# LcdModule-16x2_1V0.net
KiCad netlist of a schematic drawn in EAGLE
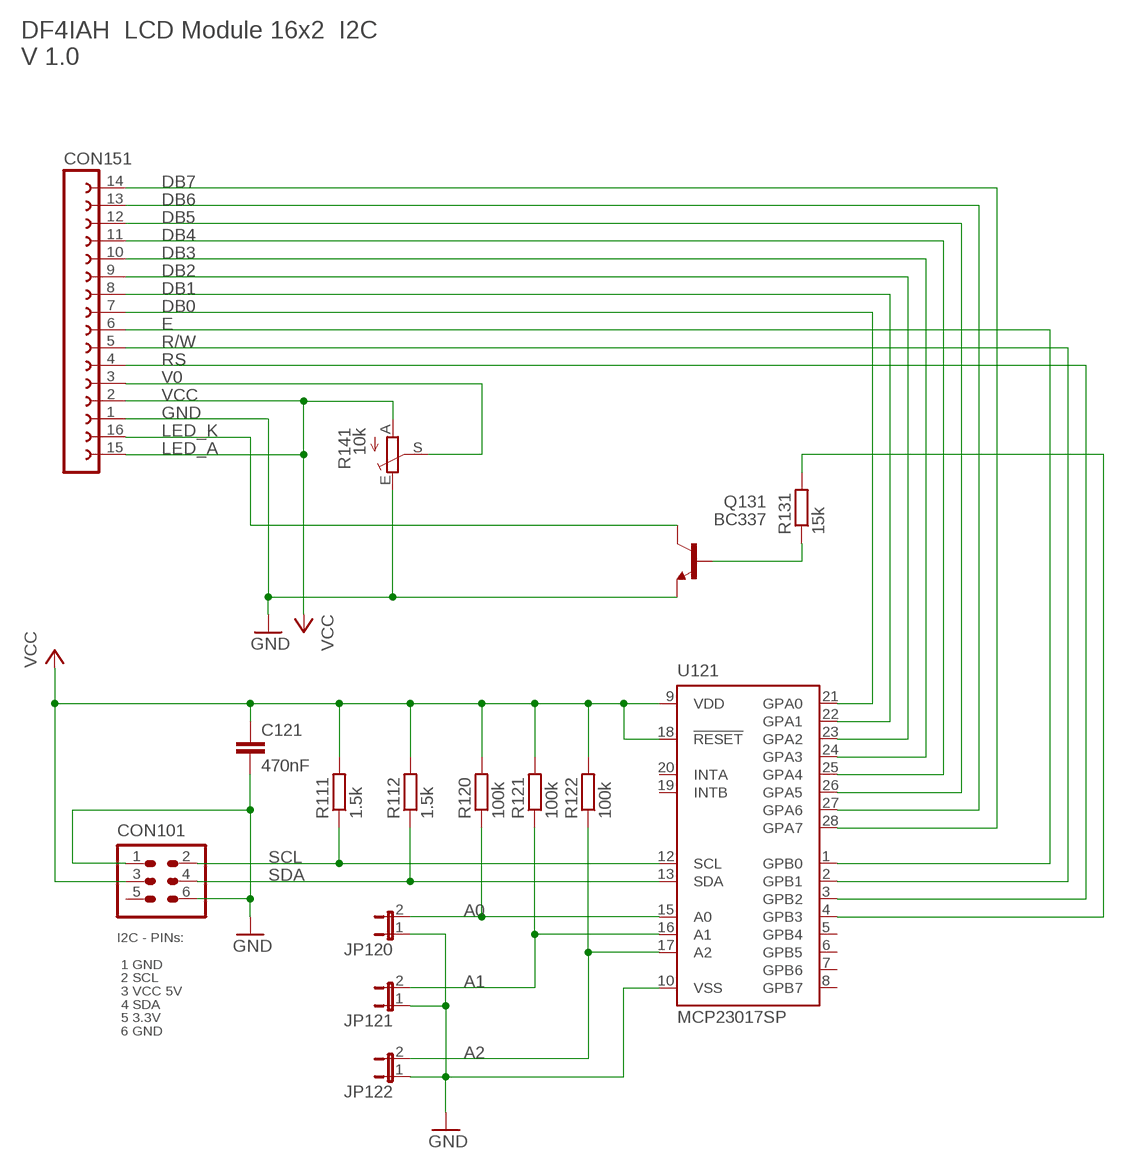
[diagram p0: schematic, sheet 1]
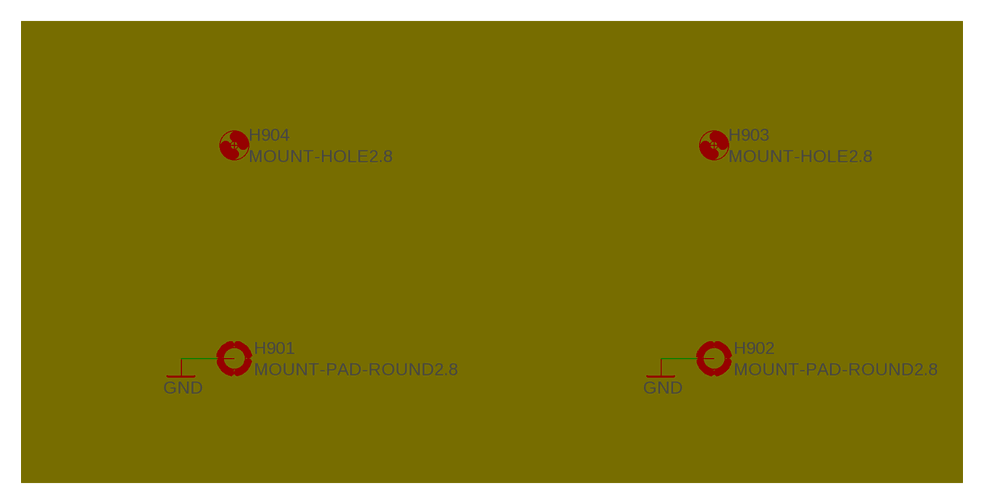
[diagram p1: schematic, sheet 2]

(export (version "E")
  (design (tool "Eeschema 10.0.6"))
  (components
    (comp (ref "C121")
      (value "470nF")
      (footprint "eagle-import:C0805")
      (libsource (lib "eagle-import") (part "C-EUC0805"))
    )
    (comp (ref "CON101")
      (value "HEADER-2X3SMD")
      (footprint "eagle-import:2X03SMD")
      (libsource (lib "eagle-import") (part "HEADER-2X3SMD"))
    )
    (comp (ref "CON151")
      (value "CON_LCDBRD_16W")
      (footprint "eagle-import:CON_LCDBRD_16W")
      (libsource (lib "eagle-import") (part "CON_LCDBRD_16W"))
    )
    (comp (ref "JP120")
      (value "JP1E")
      (footprint "eagle-import:JP1")
      (libsource (lib "eagle-import") (part "JP1E"))
    )
    (comp (ref "JP121")
      (value "JP1E")
      (footprint "eagle-import:JP1")
      (libsource (lib "eagle-import") (part "JP1E"))
    )
    (comp (ref "JP122")
      (value "JP1E")
      (footprint "eagle-import:JP1")
      (libsource (lib "eagle-import") (part "JP1E"))
    )
    (comp (ref "Q131")
      (value "BC337")
      (footprint "eagle-import:TO92")
      (libsource (lib "eagle-import") (part "BC337"))
    )
    (comp (ref "R111")
      (value "1.5k")
      (footprint "eagle-import:R0805")
      (libsource (lib "eagle-import") (part "R-EU_R0805"))
    )
    (comp (ref "R112")
      (value "1.5k")
      (footprint "eagle-import:R0805")
      (libsource (lib "eagle-import") (part "R-EU_R0805"))
    )
    (comp (ref "R120")
      (value "100k")
      (footprint "eagle-import:R0805")
      (libsource (lib "eagle-import") (part "R-EU_R0805"))
    )
    (comp (ref "R121")
      (value "100k")
      (footprint "eagle-import:R0805")
      (libsource (lib "eagle-import") (part "R-EU_R0805"))
    )
    (comp (ref "R122")
      (value "100k")
      (footprint "eagle-import:R0805")
      (libsource (lib "eagle-import") (part "R-EU_R0805"))
    )
    (comp (ref "R131")
      (value "15k")
      (footprint "eagle-import:R0805")
      (libsource (lib "eagle-import") (part "R-EU_R0805"))
    )
    (comp (ref "R141")
      (value "10k")
      (footprint "eagle-import:PT-10")
      (libsource (lib "eagle-import") (part "TRIM_EU-PT10"))
    )
    (comp (ref "U121")
      (value "MCP23017SP")
      (footprint "eagle-import:DIL28-3")
      (fields (field (name "MF") "MICROCHIP") (field (name "MPN") "MCP23017-E/SP"))
      (libsource (lib "eagle-import") (part "MCP23017SP"))
    )
    (comp (ref "H901")
      (value "MOUNT-PAD-ROUND2.8")
      (footprint "eagle-import:2,8-PAD")
      (libsource (lib "eagle-import") (part "MOUNT-PAD-ROUND2.8"))
    )
    (comp (ref "H902")
      (value "MOUNT-PAD-ROUND2.8")
      (footprint "eagle-import:2,8-PAD")
      (libsource (lib "eagle-import") (part "MOUNT-PAD-ROUND2.8"))
    )
    (comp (ref "H903")
      (value "MOUNT-HOLE2.8")
      (footprint "eagle-import:2,8")
      (libsource (lib "eagle-import") (part "MOUNT-HOLE2.8"))
    )
    (comp (ref "H904")
      (value "MOUNT-HOLE2.8")
      (footprint "eagle-import:2,8")
      (libsource (lib "eagle-import") (part "MOUNT-HOLE2.8"))
    )
  )
  (nets
    (net (code "1") (name "A0") (class "Default")
      (node (ref "JP120") (pin "2") (pinfunction "2_2") (pintype "passive"))
      (node (ref "R120") (pin "1") (pinfunction "1_1") (pintype "passive"))
      (node (ref "U121") (pin "15") (pinfunction "A0_15") (pintype "input"))
    )
    (net (code "2") (name "A1") (class "Default")
      (node (ref "JP121") (pin "2") (pinfunction "2_2") (pintype "passive"))
      (node (ref "R121") (pin "1") (pinfunction "1_1") (pintype "passive"))
      (node (ref "U121") (pin "16") (pinfunction "A1_16") (pintype "input"))
    )
    (net (code "3") (name "A2") (class "Default")
      (node (ref "JP122") (pin "2") (pinfunction "2_2") (pintype "passive"))
      (node (ref "R122") (pin "1") (pinfunction "1_1") (pintype "passive"))
      (node (ref "U121") (pin "17") (pinfunction "A2_17") (pintype "input"))
    )
    (net (code "4") (name "DB0") (class "Default")
      (node (ref "CON151") (pin "7") (pinfunction "7_7") (pintype "passive"))
      (node (ref "U121") (pin "21") (pinfunction "GPA0_21") (pintype "bidirectional"))
    )
    (net (code "5") (name "DB1") (class "Default")
      (node (ref "CON151") (pin "8") (pinfunction "8_8") (pintype "passive"))
      (node (ref "U121") (pin "22") (pinfunction "GPA1_22") (pintype "bidirectional"))
    )
    (net (code "6") (name "DB2") (class "Default")
      (node (ref "CON151") (pin "9") (pinfunction "9_9") (pintype "passive"))
      (node (ref "U121") (pin "23") (pinfunction "GPA2_23") (pintype "bidirectional"))
    )
    (net (code "7") (name "DB3") (class "Default")
      (node (ref "CON151") (pin "10") (pinfunction "10_10") (pintype "passive"))
      (node (ref "U121") (pin "24") (pinfunction "GPA3_24") (pintype "bidirectional"))
    )
    (net (code "8") (name "DB4") (class "Default")
      (node (ref "CON151") (pin "11") (pinfunction "11_11") (pintype "passive"))
      (node (ref "U121") (pin "25") (pinfunction "GPA4_25") (pintype "bidirectional"))
    )
    (net (code "9") (name "DB5") (class "Default")
      (node (ref "CON151") (pin "12") (pinfunction "12_12") (pintype "passive"))
      (node (ref "U121") (pin "26") (pinfunction "GPA5_26") (pintype "bidirectional"))
    )
    (net (code "10") (name "DB6") (class "Default")
      (node (ref "CON151") (pin "13") (pinfunction "13_13") (pintype "passive"))
      (node (ref "U121") (pin "27") (pinfunction "GPA6_27") (pintype "bidirectional"))
    )
    (net (code "11") (name "DB7") (class "Default")
      (node (ref "CON151") (pin "14") (pinfunction "14_14") (pintype "passive"))
      (node (ref "U121") (pin "28") (pinfunction "GPA7_28") (pintype "bidirectional"))
    )
    (net (code "12") (name "E") (class "Default")
      (node (ref "CON151") (pin "6") (pinfunction "6_6") (pintype "passive"))
      (node (ref "U121") (pin "1") (pinfunction "GPB0_1") (pintype "bidirectional"))
    )
    (net (code "13") (name "GND") (class "Default")
      (node (ref "C121") (pin "2") (pinfunction "2_2") (pintype "passive"))
      (node (ref "CON101") (pin "1") (pinfunction "1_1") (pintype "passive"))
      (node (ref "CON101") (pin "6") (pinfunction "6_6") (pintype "passive"))
      (node (ref "CON151") (pin "1") (pinfunction "1_1") (pintype "passive"))
      (node (ref "H901") (pin "B2,8") (pinfunction "MOUNT_B2,8") (pintype "passive"))
      (node (ref "H902") (pin "B2,8") (pinfunction "MOUNT_B2,8") (pintype "passive"))
      (node (ref "JP120") (pin "1") (pinfunction "1_1") (pintype "passive"))
      (node (ref "JP121") (pin "1") (pinfunction "1_1") (pintype "passive"))
      (node (ref "JP122") (pin "1") (pinfunction "1_1") (pintype "passive"))
      (node (ref "Q131") (pin "1") (pinfunction "E_1") (pintype "passive"))
      (node (ref "R141") (pin "E") (pinfunction "E_E") (pintype "passive"))
      (node (ref "U121") (pin "10") (pinfunction "VSS_10") (pintype "power_in"))
    )
    (net (code "14") (name "LED_K") (class "Default")
      (node (ref "CON151") (pin "16") (pinfunction "16_16") (pintype "passive"))
      (node (ref "Q131") (pin "3") (pinfunction "C_3") (pintype "passive"))
    )
    (net (code "15") (name "Net-(Q131-B)") (class "Default")
      (node (ref "Q131") (pin "2") (pinfunction "B_2") (pintype "passive"))
      (node (ref "R131") (pin "1") (pinfunction "1_1") (pintype "passive"))
    )
    (net (code "16") (name "Net-(U121-GPB3)") (class "Default")
      (node (ref "R131") (pin "2") (pinfunction "2_2") (pintype "passive"))
      (node (ref "U121") (pin "4") (pinfunction "GPB3_4") (pintype "bidirectional"))
    )
    (net (code "17") (name "RS") (class "Default")
      (node (ref "CON151") (pin "4") (pinfunction "4_4") (pintype "passive"))
      (node (ref "U121") (pin "3") (pinfunction "GPB2_3") (pintype "bidirectional"))
    )
    (net (code "18") (name "R{slash}W") (class "Default")
      (node (ref "CON151") (pin "5") (pinfunction "5_5") (pintype "passive"))
      (node (ref "U121") (pin "2") (pinfunction "GPB1_2") (pintype "bidirectional"))
    )
    (net (code "19") (name "SCL") (class "Default")
      (node (ref "CON101") (pin "2") (pinfunction "2_2") (pintype "passive"))
      (node (ref "R111") (pin "1") (pinfunction "1_1") (pintype "passive"))
      (node (ref "U121") (pin "12") (pinfunction "SCL_12") (pintype "input"))
    )
    (net (code "20") (name "SDA") (class "Default")
      (node (ref "CON101") (pin "4") (pinfunction "4_4") (pintype "passive"))
      (node (ref "R112") (pin "1") (pinfunction "1_1") (pintype "passive"))
      (node (ref "U121") (pin "13") (pinfunction "SDA_13") (pintype "bidirectional"))
    )
    (net (code "21") (name "V0") (class "Default")
      (node (ref "CON151") (pin "3") (pinfunction "3_3") (pintype "passive"))
      (node (ref "R141") (pin "S") (pinfunction "S_S") (pintype "passive"))
    )
    (net (code "22") (name "VCC") (class "Default")
      (node (ref "C121") (pin "1") (pinfunction "1_1") (pintype "passive"))
      (node (ref "CON101") (pin "3") (pinfunction "3_3") (pintype "passive"))
      (node (ref "CON151") (pin "15") (pinfunction "15_15") (pintype "passive"))
      (node (ref "CON151") (pin "2") (pinfunction "2_2") (pintype "passive"))
      (node (ref "R111") (pin "2") (pinfunction "2_2") (pintype "passive"))
      (node (ref "R112") (pin "2") (pinfunction "2_2") (pintype "passive"))
      (node (ref "R120") (pin "2") (pinfunction "2_2") (pintype "passive"))
      (node (ref "R121") (pin "2") (pinfunction "2_2") (pintype "passive"))
      (node (ref "R122") (pin "2") (pinfunction "2_2") (pintype "passive"))
      (node (ref "R141") (pin "A") (pinfunction "A_A") (pintype "passive"))
      (node (ref "U121") (pin "18") (pinfunction "~{RESET}_18") (pintype "input"))
      (node (ref "U121") (pin "9") (pinfunction "VDD_9") (pintype "power_in"))
    )
    (net (code "23") (name "unconnected-(CON101-Pad5)") (class "Default")
      (node (ref "CON101") (pin "5") (pinfunction "5_5") (pintype "passive"))
    )
    (net (code "24") (name "unconnected-(U121-GPB4-Pad5)") (class "Default")
      (node (ref "U121") (pin "5") (pinfunction "GPB4_5") (pintype "bidirectional"))
    )
    (net (code "25") (name "unconnected-(U121-GPB5-Pad6)") (class "Default")
      (node (ref "U121") (pin "6") (pinfunction "GPB5_6") (pintype "bidirectional"))
    )
    (net (code "26") (name "unconnected-(U121-GPB6-Pad7)") (class "Default")
      (node (ref "U121") (pin "7") (pinfunction "GPB6_7") (pintype "bidirectional"))
    )
    (net (code "27") (name "unconnected-(U121-GPB7-Pad8)") (class "Default")
      (node (ref "U121") (pin "8") (pinfunction "GPB7_8") (pintype "bidirectional"))
    )
    (net (code "28") (name "unconnected-(U121-INTA-Pad20)") (class "Default")
      (node (ref "U121") (pin "20") (pinfunction "INTA_20") (pintype "output"))
    )
    (net (code "29") (name "unconnected-(U121-INTB-Pad19)") (class "Default")
      (node (ref "U121") (pin "19") (pinfunction "INTB_19") (pintype "output"))
    )
  )
)
